# maxim_breakout.net
KiCad netlist of a schematic drawn in EAGLE
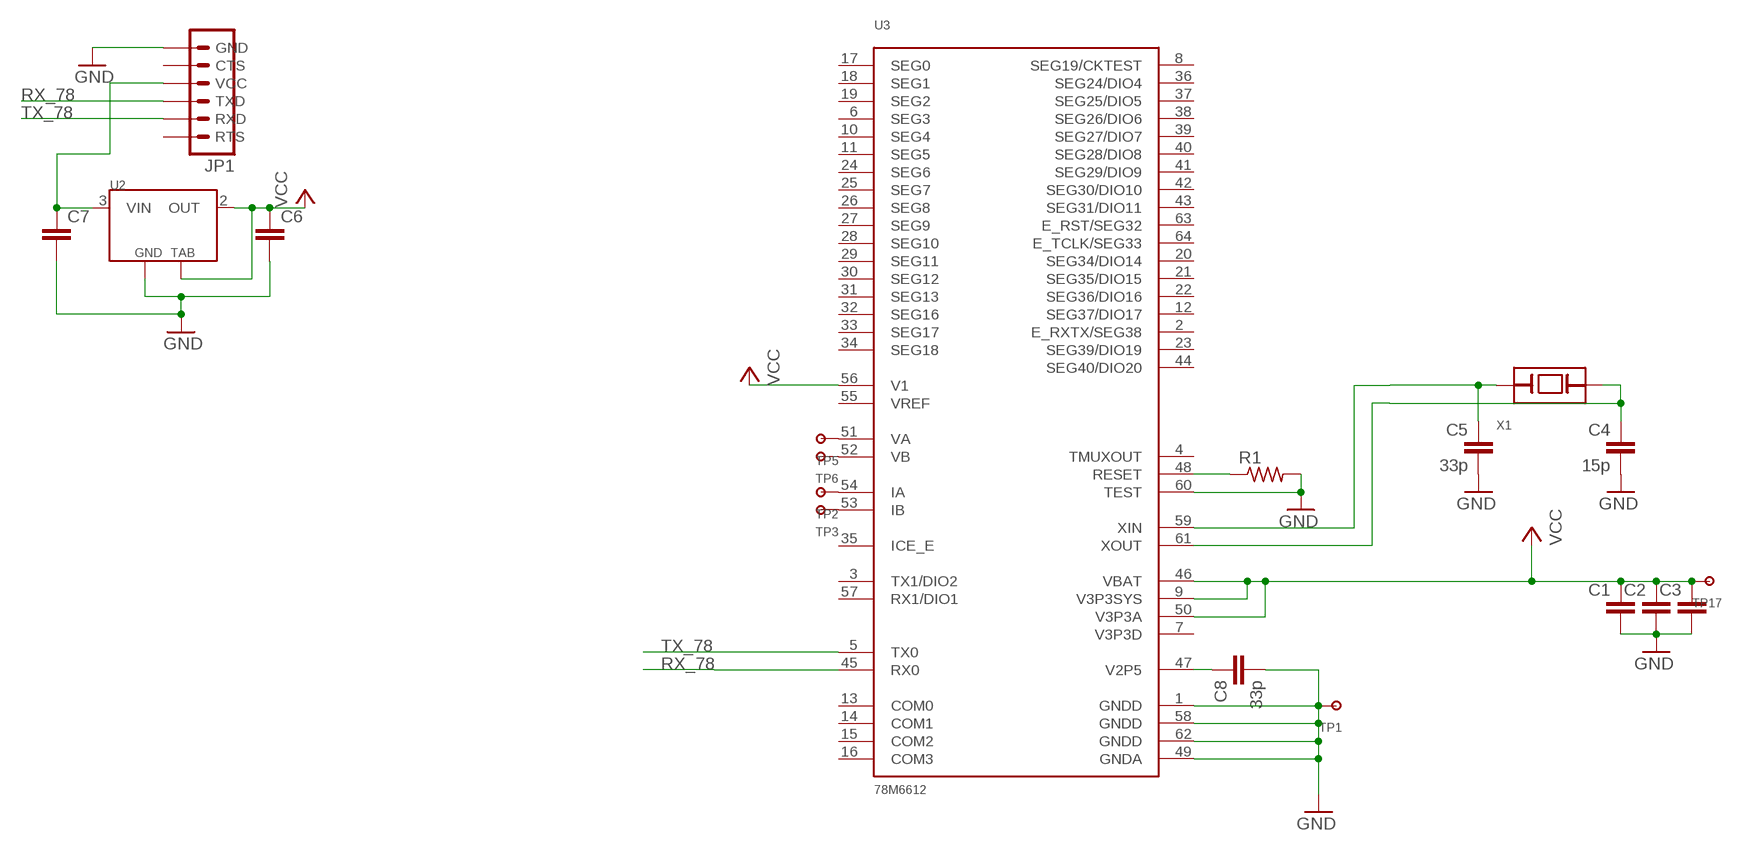
[diagram p0: schematic, sheet 1]

(export (version "E")
  (design (tool "Eeschema 10.0.6"))
  (components
    (comp (ref "C1")
      (value "CAP0805")
      (footprint "eagle-import:0805")
      (libsource (lib "eagle-import") (part "CAP0805"))
    )
    (comp (ref "C2")
      (value "CAP0805")
      (footprint "eagle-import:0805")
      (libsource (lib "eagle-import") (part "CAP0805"))
    )
    (comp (ref "C3")
      (value "CAP0805")
      (footprint "eagle-import:0805")
      (libsource (lib "eagle-import") (part "CAP0805"))
    )
    (comp (ref "C4")
      (value "15p")
      (footprint "eagle-import:0805")
      (libsource (lib "eagle-import") (part "CAP0805"))
    )
    (comp (ref "C5")
      (value "33p")
      (footprint "eagle-import:0805")
      (libsource (lib "eagle-import") (part "CAP0805"))
    )
    (comp (ref "C6")
      (value "CAP0805")
      (footprint "eagle-import:0805")
      (libsource (lib "eagle-import") (part "CAP0805"))
    )
    (comp (ref "C7")
      (value "CAP0805")
      (footprint "eagle-import:0805")
      (libsource (lib "eagle-import") (part "CAP0805"))
    )
    (comp (ref "C8")
      (value "33p")
      (footprint "eagle-import:0805")
      (libsource (lib "eagle-import") (part "CAP0805"))
    )
    (comp (ref "JP1")
      (value "FTDI_CABLELOCK_LONGPADS")
      (footprint "eagle-import:1X06_LOCK_LONGPADS")
      (libsource (lib "eagle-import") (part "FTDI_CABLELOCK_LONGPADS"))
    )
    (comp (ref "R1")
      (value "R-US_R0805")
      (footprint "eagle-import:R0805")
      (libsource (lib "eagle-import") (part "R-US_R0805"))
    )
    (comp (ref "TP1")
      (value "TESTPOINT100MIL")
      (footprint "eagle-import:TESTPOINT-100MIL")
      (libsource (lib "eagle-import") (part "TESTPOINT100MIL"))
    )
    (comp (ref "TP2")
      (value "TESTPOINT100MIL")
      (footprint "eagle-import:TESTPOINT-100MIL")
      (libsource (lib "eagle-import") (part "TESTPOINT100MIL"))
    )
    (comp (ref "TP3")
      (value "TESTPOINT100MIL")
      (footprint "eagle-import:TESTPOINT-100MIL")
      (libsource (lib "eagle-import") (part "TESTPOINT100MIL"))
    )
    (comp (ref "TP5")
      (value "TESTPOINT100MIL")
      (footprint "eagle-import:TESTPOINT-100MIL")
      (libsource (lib "eagle-import") (part "TESTPOINT100MIL"))
    )
    (comp (ref "TP6")
      (value "TESTPOINT100MIL")
      (footprint "eagle-import:TESTPOINT-100MIL")
      (libsource (lib "eagle-import") (part "TESTPOINT100MIL"))
    )
    (comp (ref "TP17")
      (value "TESTPOINT100MIL")
      (footprint "eagle-import:TESTPOINT-100MIL")
      (libsource (lib "eagle-import") (part "TESTPOINT100MIL"))
    )
    (comp (ref "U2")
      (value "NX1117C")
      (footprint "eagle-import:SOT223")
      (libsource (lib "eagle-import") (part "NX1117C"))
    )
    (comp (ref "U3")
      (value "78M6612")
      (footprint "eagle-import:78M6612")
      (libsource (lib "eagle-import") (part "78M6612"))
    )
    (comp (ref "X1")
      (value "XTALABS07")
      (footprint "eagle-import:ABS07")
      (libsource (lib "eagle-import") (part "XTALABS07"))
    )
  )
  (nets
    (net (code "1") (name "/RX_78") (class "Default")
      (node (ref "JP1") (pin "4") (pinfunction "TXD_4") (pintype "passive"))
      (node (ref "U3") (pin "45") (pinfunction "RX0_45") (pintype "bidirectional"))
    )
    (net (code "2") (name "/TX_78") (class "Default")
      (node (ref "JP1") (pin "5") (pinfunction "RXD_5") (pintype "passive"))
      (node (ref "U3") (pin "5") (pinfunction "TX0_5") (pintype "bidirectional"))
    )
    (net (code "3") (name "GND") (class "Default")
      (node (ref "C1") (pin "2") (pinfunction "2_2") (pintype "passive"))
      (node (ref "C2") (pin "2") (pinfunction "2_2") (pintype "passive"))
      (node (ref "C3") (pin "2") (pinfunction "2_2") (pintype "passive"))
      (node (ref "C4") (pin "2") (pinfunction "2_2") (pintype "passive"))
      (node (ref "C5") (pin "2") (pinfunction "2_2") (pintype "passive"))
      (node (ref "C6") (pin "2") (pinfunction "2_2") (pintype "passive"))
      (node (ref "C7") (pin "2") (pinfunction "2_2") (pintype "passive"))
      (node (ref "C8") (pin "2") (pinfunction "2_2") (pintype "passive"))
      (node (ref "JP1") (pin "1") (pinfunction "GND_1") (pintype "passive"))
      (node (ref "R1") (pin "2") (pinfunction "2_2") (pintype "passive"))
      (node (ref "TP1") (pin "2") (pinfunction "P$1_2") (pintype "bidirectional"))
      (node (ref "U2") (pin "1") (pinfunction "GND_1") (pintype "bidirectional"))
      (node (ref "U3") (pin "1") (pinfunction "GNDD_1") (pintype "bidirectional"))
      (node (ref "U3") (pin "49") (pinfunction "GNDA_49") (pintype "bidirectional"))
      (node (ref "U3") (pin "58") (pinfunction "GNDD_58") (pintype "bidirectional"))
      (node (ref "U3") (pin "60") (pinfunction "TEST_60") (pintype "bidirectional"))
      (node (ref "U3") (pin "62") (pinfunction "GNDD_62") (pintype "bidirectional"))
    )
    (net (code "4") (name "Net-(JP1-VCC)") (class "Default")
      (node (ref "C7") (pin "1") (pinfunction "1_1") (pintype "passive"))
      (node (ref "JP1") (pin "3") (pinfunction "VCC_3") (pintype "passive"))
      (node (ref "U2") (pin "3") (pinfunction "VIN_3") (pintype "bidirectional"))
    )
    (net (code "5") (name "Net-(TP2-P$1)") (class "Default")
      (node (ref "TP2") (pin "2") (pinfunction "P$1_2") (pintype "bidirectional"))
      (node (ref "U3") (pin "54") (pinfunction "IA_54") (pintype "bidirectional"))
    )
    (net (code "6") (name "Net-(TP3-P$1)") (class "Default")
      (node (ref "TP3") (pin "2") (pinfunction "P$1_2") (pintype "bidirectional"))
      (node (ref "U3") (pin "53") (pinfunction "IB_53") (pintype "bidirectional"))
    )
    (net (code "7") (name "Net-(TP5-P$1)") (class "Default")
      (node (ref "TP5") (pin "2") (pinfunction "P$1_2") (pintype "bidirectional"))
      (node (ref "U3") (pin "51") (pinfunction "VA_51") (pintype "bidirectional"))
    )
    (net (code "8") (name "Net-(TP6-P$1)") (class "Default")
      (node (ref "TP6") (pin "2") (pinfunction "P$1_2") (pintype "bidirectional"))
      (node (ref "U3") (pin "52") (pinfunction "VB_52") (pintype "bidirectional"))
    )
    (net (code "9") (name "Net-(U3-RESET)") (class "Default")
      (node (ref "R1") (pin "1") (pinfunction "1_1") (pintype "passive"))
      (node (ref "U3") (pin "48") (pinfunction "RESET_48") (pintype "bidirectional"))
    )
    (net (code "10") (name "Net-(U3-V2P5)") (class "Default")
      (node (ref "C8") (pin "1") (pinfunction "1_1") (pintype "passive"))
      (node (ref "U3") (pin "47") (pinfunction "V2P5_47") (pintype "bidirectional"))
    )
    (net (code "11") (name "Net-(U3-XIN)") (class "Default")
      (node (ref "C5") (pin "1") (pinfunction "1_1") (pintype "passive"))
      (node (ref "U3") (pin "59") (pinfunction "XIN_59") (pintype "bidirectional"))
      (node (ref "X1") (pin "1") (pinfunction "A_1") (pintype "bidirectional"))
    )
    (net (code "12") (name "Net-(U3-XOUT)") (class "Default")
      (node (ref "C4") (pin "1") (pinfunction "1_1") (pintype "passive"))
      (node (ref "U3") (pin "61") (pinfunction "XOUT_61") (pintype "bidirectional"))
      (node (ref "X1") (pin "2") (pinfunction "B_2") (pintype "bidirectional"))
    )
    (net (code "13") (name "VCC") (class "Default")
      (node (ref "C1") (pin "1") (pinfunction "1_1") (pintype "passive"))
      (node (ref "C2") (pin "1") (pinfunction "1_1") (pintype "passive"))
      (node (ref "C3") (pin "1") (pinfunction "1_1") (pintype "passive"))
      (node (ref "C6") (pin "1") (pinfunction "1_1") (pintype "passive"))
      (node (ref "TP17") (pin "2") (pinfunction "P$1_2") (pintype "bidirectional"))
      (node (ref "U2") (pin "2") (pinfunction "OUT_2") (pintype "bidirectional"))
      (node (ref "U2") (pin "4") (pinfunction "TAB_4") (pintype "bidirectional"))
      (node (ref "U3") (pin "46") (pinfunction "VBAT_46") (pintype "bidirectional"))
      (node (ref "U3") (pin "50") (pinfunction "V3P3A_50") (pintype "bidirectional"))
      (node (ref "U3") (pin "56") (pinfunction "V1_56") (pintype "bidirectional"))
      (node (ref "U3") (pin "9") (pinfunction "V3P3SYS_9") (pintype "bidirectional"))
    )
    (net (code "14") (name "unconnected-(JP1-CTS-Pad2)") (class "Default")
      (node (ref "JP1") (pin "2") (pinfunction "CTS_2") (pintype "passive"))
    )
    (net (code "15") (name "unconnected-(JP1-RTS-Pad6)") (class "Default")
      (node (ref "JP1") (pin "6") (pinfunction "RTS_6") (pintype "passive"))
    )
    (net (code "16") (name "unconnected-(U3-COM0-Pad13)") (class "Default")
      (node (ref "U3") (pin "13") (pinfunction "COM0_13") (pintype "bidirectional"))
    )
    (net (code "17") (name "unconnected-(U3-COM1-Pad14)") (class "Default")
      (node (ref "U3") (pin "14") (pinfunction "COM1_14") (pintype "bidirectional"))
    )
    (net (code "18") (name "unconnected-(U3-COM2-Pad15)") (class "Default")
      (node (ref "U3") (pin "15") (pinfunction "COM2_15") (pintype "bidirectional"))
    )
    (net (code "19") (name "unconnected-(U3-COM3-Pad16)") (class "Default")
      (node (ref "U3") (pin "16") (pinfunction "COM3_16") (pintype "bidirectional"))
    )
    (net (code "20") (name "unconnected-(U3-E_RST{slash}SEG32-Pad63)") (class "Default")
      (node (ref "U3") (pin "63") (pinfunction "E_RST/SEG32_63") (pintype "bidirectional"))
    )
    (net (code "21") (name "unconnected-(U3-E_RXTX{slash}SEG38-Pad2)") (class "Default")
      (node (ref "U3") (pin "2") (pinfunction "E_RXTX/SEG38_2") (pintype "bidirectional"))
    )
    (net (code "22") (name "unconnected-(U3-E_TCLK{slash}SEG33-Pad64)") (class "Default")
      (node (ref "U3") (pin "64") (pinfunction "E_TCLK/SEG33_64") (pintype "bidirectional"))
    )
    (net (code "23") (name "unconnected-(U3-ICE_E-Pad35)") (class "Default")
      (node (ref "U3") (pin "35") (pinfunction "ICE_E_35") (pintype "bidirectional"))
    )
    (net (code "24") (name "unconnected-(U3-RX1{slash}DIO1-Pad57)") (class "Default")
      (node (ref "U3") (pin "57") (pinfunction "RX1/DIO1_57") (pintype "bidirectional"))
    )
    (net (code "25") (name "unconnected-(U3-SEG0-Pad17)") (class "Default")
      (node (ref "U3") (pin "17") (pinfunction "SEG0_17") (pintype "bidirectional"))
    )
    (net (code "26") (name "unconnected-(U3-SEG1-Pad18)") (class "Default")
      (node (ref "U3") (pin "18") (pinfunction "SEG1_18") (pintype "bidirectional"))
    )
    (net (code "27") (name "unconnected-(U3-SEG2-Pad19)") (class "Default")
      (node (ref "U3") (pin "19") (pinfunction "SEG2_19") (pintype "bidirectional"))
    )
    (net (code "28") (name "unconnected-(U3-SEG3-Pad6)") (class "Default")
      (node (ref "U3") (pin "6") (pinfunction "SEG3_6") (pintype "bidirectional"))
    )
    (net (code "29") (name "unconnected-(U3-SEG4-Pad10)") (class "Default")
      (node (ref "U3") (pin "10") (pinfunction "SEG4_10") (pintype "bidirectional"))
    )
    (net (code "30") (name "unconnected-(U3-SEG5-Pad11)") (class "Default")
      (node (ref "U3") (pin "11") (pinfunction "SEG5_11") (pintype "bidirectional"))
    )
    (net (code "31") (name "unconnected-(U3-SEG6-Pad24)") (class "Default")
      (node (ref "U3") (pin "24") (pinfunction "SEG6_24") (pintype "bidirectional"))
    )
    (net (code "32") (name "unconnected-(U3-SEG7-Pad25)") (class "Default")
      (node (ref "U3") (pin "25") (pinfunction "SEG7_25") (pintype "bidirectional"))
    )
    (net (code "33") (name "unconnected-(U3-SEG8-Pad26)") (class "Default")
      (node (ref "U3") (pin "26") (pinfunction "SEG8_26") (pintype "bidirectional"))
    )
    (net (code "34") (name "unconnected-(U3-SEG9-Pad27)") (class "Default")
      (node (ref "U3") (pin "27") (pinfunction "SEG9_27") (pintype "bidirectional"))
    )
    (net (code "35") (name "unconnected-(U3-SEG10-Pad28)") (class "Default")
      (node (ref "U3") (pin "28") (pinfunction "SEG10_28") (pintype "bidirectional"))
    )
    (net (code "36") (name "unconnected-(U3-SEG11-Pad29)") (class "Default")
      (node (ref "U3") (pin "29") (pinfunction "SEG11_29") (pintype "bidirectional"))
    )
    (net (code "37") (name "unconnected-(U3-SEG12-Pad30)") (class "Default")
      (node (ref "U3") (pin "30") (pinfunction "SEG12_30") (pintype "bidirectional"))
    )
    (net (code "38") (name "unconnected-(U3-SEG13-Pad31)") (class "Default")
      (node (ref "U3") (pin "31") (pinfunction "SEG13_31") (pintype "bidirectional"))
    )
    (net (code "39") (name "unconnected-(U3-SEG16-Pad32)") (class "Default")
      (node (ref "U3") (pin "32") (pinfunction "SEG16_32") (pintype "bidirectional"))
    )
    (net (code "40") (name "unconnected-(U3-SEG17-Pad33)") (class "Default")
      (node (ref "U3") (pin "33") (pinfunction "SEG17_33") (pintype "bidirectional"))
    )
    (net (code "41") (name "unconnected-(U3-SEG18-Pad34)") (class "Default")
      (node (ref "U3") (pin "34") (pinfunction "SEG18_34") (pintype "bidirectional"))
    )
    (net (code "42") (name "unconnected-(U3-SEG19{slash}CKTEST-Pad8)") (class "Default")
      (node (ref "U3") (pin "8") (pinfunction "SEG19/CKTEST_8") (pintype "bidirectional"))
    )
    (net (code "43") (name "unconnected-(U3-SEG24{slash}DIO4-Pad36)") (class "Default")
      (node (ref "U3") (pin "36") (pinfunction "SEG24/DIO4_36") (pintype "bidirectional"))
    )
    (net (code "44") (name "unconnected-(U3-SEG25{slash}DIO5-Pad37)") (class "Default")
      (node (ref "U3") (pin "37") (pinfunction "SEG25/DIO5_37") (pintype "bidirectional"))
    )
    (net (code "45") (name "unconnected-(U3-SEG26{slash}DIO6-Pad38)") (class "Default")
      (node (ref "U3") (pin "38") (pinfunction "SEG26/DIO6_38") (pintype "bidirectional"))
    )
    (net (code "46") (name "unconnected-(U3-SEG27{slash}DIO7-Pad39)") (class "Default")
      (node (ref "U3") (pin "39") (pinfunction "SEG27/DIO7_39") (pintype "bidirectional"))
    )
    (net (code "47") (name "unconnected-(U3-SEG28{slash}DIO8-Pad40)") (class "Default")
      (node (ref "U3") (pin "40") (pinfunction "SEG28/DIO8_40") (pintype "bidirectional"))
    )
    (net (code "48") (name "unconnected-(U3-SEG29{slash}DIO9-Pad41)") (class "Default")
      (node (ref "U3") (pin "41") (pinfunction "SEG29/DIO9_41") (pintype "bidirectional"))
    )
    (net (code "49") (name "unconnected-(U3-SEG30{slash}DIO10-Pad42)") (class "Default")
      (node (ref "U3") (pin "42") (pinfunction "SEG30/DIO10_42") (pintype "bidirectional"))
    )
    (net (code "50") (name "unconnected-(U3-SEG31{slash}DIO11-Pad43)") (class "Default")
      (node (ref "U3") (pin "43") (pinfunction "SEG31/DIO11_43") (pintype "bidirectional"))
    )
    (net (code "51") (name "unconnected-(U3-SEG34{slash}DIO14-Pad20)") (class "Default")
      (node (ref "U3") (pin "20") (pinfunction "SEG34/DIO14_20") (pintype "bidirectional"))
    )
    (net (code "52") (name "unconnected-(U3-SEG35{slash}DIO15-Pad21)") (class "Default")
      (node (ref "U3") (pin "21") (pinfunction "SEG35/DIO15_21") (pintype "bidirectional"))
    )
    (net (code "53") (name "unconnected-(U3-SEG36{slash}DIO16-Pad22)") (class "Default")
      (node (ref "U3") (pin "22") (pinfunction "SEG36/DIO16_22") (pintype "bidirectional"))
    )
    (net (code "54") (name "unconnected-(U3-SEG37{slash}DIO17-Pad12)") (class "Default")
      (node (ref "U3") (pin "12") (pinfunction "SEG37/DIO17_12") (pintype "bidirectional"))
    )
    (net (code "55") (name "unconnected-(U3-SEG39{slash}DIO19-Pad23)") (class "Default")
      (node (ref "U3") (pin "23") (pinfunction "SEG39/DIO19_23") (pintype "bidirectional"))
    )
    (net (code "56") (name "unconnected-(U3-SEG40{slash}DIO20-Pad44)") (class "Default")
      (node (ref "U3") (pin "44") (pinfunction "SEG40/DIO20_44") (pintype "bidirectional"))
    )
    (net (code "57") (name "unconnected-(U3-TMUXOUT-Pad4)") (class "Default")
      (node (ref "U3") (pin "4") (pinfunction "TMUXOUT_4") (pintype "bidirectional"))
    )
    (net (code "58") (name "unconnected-(U3-TX1{slash}DIO2-Pad3)") (class "Default")
      (node (ref "U3") (pin "3") (pinfunction "TX1/DIO2_3") (pintype "bidirectional"))
    )
    (net (code "59") (name "unconnected-(U3-V3P3D-Pad7)") (class "Default")
      (node (ref "U3") (pin "7") (pinfunction "V3P3D_7") (pintype "bidirectional"))
    )
    (net (code "60") (name "unconnected-(U3-VREF-Pad55)") (class "Default")
      (node (ref "U3") (pin "55") (pinfunction "VREF_55") (pintype "bidirectional"))
    )
  )
)
